# car.net
KiCad netlist of a schematic drawn in EAGLE
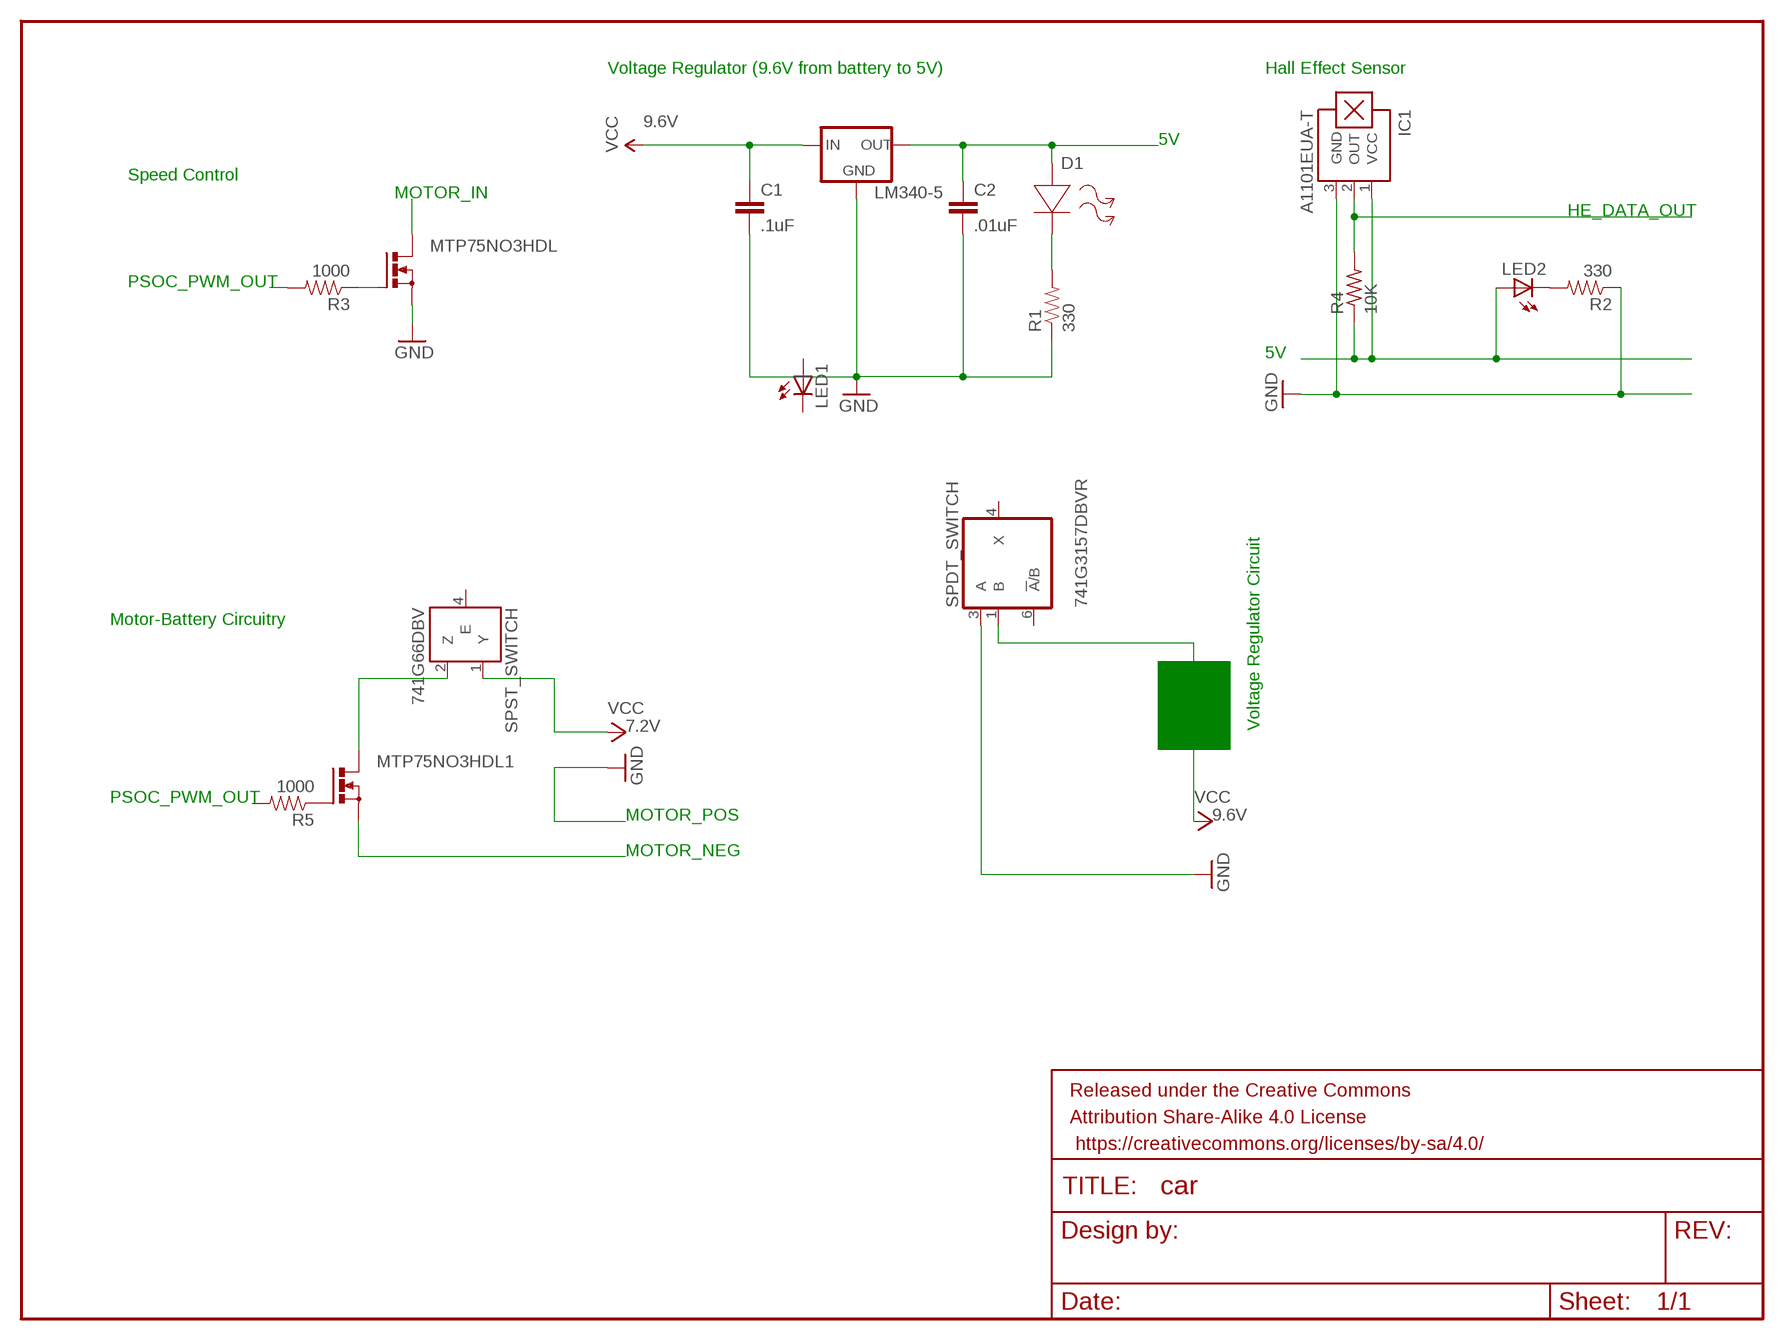
[diagram p0: schematic, sheet 1]

(export (version "E")
  (design (tool "Eeschema 10.0.6"))
  (components
    (comp (ref "C1")
      (value ".1uF")
      (footprint "eagle-import:0402-CAP")
      (libsource (lib "eagle-import") (part "CAP0402-CAP"))
    )
    (comp (ref "C2")
      (value ".01uF")
      (footprint "eagle-import:0402-CAP")
      (libsource (lib "eagle-import") (part "CAP0402-CAP"))
    )
    (comp (ref "D1")
      (value "LED")
      (footprint "eagle-import:R0805")
      (libsource (lib "eagle-import") (part "LED"))
    )
    (comp (ref "FRAME1")
      (value "FRAME-LETTER")
      (footprint "eagle-import:CREATIVE_COMMONS")
      (fields (field (name "DESIGNER") "NAME"))
      (libsource (lib "eagle-import") (part "FRAME-LETTER"))
    )
    (comp (ref "IC1")
      (value "A1101EUA-T")
      (footprint "eagle-import:SOT23-W")
      (fields (field (name "MF") "ALLEGRO MICROSYSTEMS, INC.") (field (name "MPN") "A1301ELHLT-T"))
      (libsource (lib "eagle-import") (part "A13?LH01"))
    )
    (comp (ref "LED1")
      (value "LED_E")
      (footprint "eagle-import:LED_1206")
      (libsource (lib "eagle-import") (part "LED_E"))
    )
    (comp (ref "LED2")
      (value "LED_E")
      (footprint "eagle-import:LED_1206")
      (libsource (lib "eagle-import") (part "LED_E"))
    )
    (comp (ref "LM340-5")
      (value "V_REG_78XX-TO-220")
      (footprint "eagle-import:TO-220-ALT")
      (libsource (lib "eagle-import") (part "V_REG_78XX-TO-220"))
    )
    (comp (ref "MTP75NO3HDL")
      (value "PMOSFET_NTO220BH")
      (footprint "eagle-import:TO220BH")
      (libsource (lib "eagle-import") (part "PMOSFET_NTO220BH"))
    )
    (comp (ref "MTP75NO3HDL1")
      (value "PMOSFET_NTO220BH")
      (footprint "eagle-import:TO220BH")
      (libsource (lib "eagle-import") (part "PMOSFET_NTO220BH"))
    )
    (comp (ref "R1")
      (value "330")
      (footprint "eagle-import:0402-RES")
      (libsource (lib "eagle-import") (part "RESISTOR0402-RES"))
    )
    (comp (ref "R2")
      (value "330")
      (footprint "eagle-import:0402-RES")
      (libsource (lib "eagle-import") (part "RESISTOR0402-RES"))
    )
    (comp (ref "R3")
      (value "1000")
      (footprint "eagle-import:0402-RES")
      (libsource (lib "eagle-import") (part "RESISTOR0402-RES"))
    )
    (comp (ref "R4")
      (value "10K")
      (footprint "eagle-import:0204V")
      (libsource (lib "eagle-import") (part "R-US_0204/2V"))
    )
    (comp (ref "R5")
      (value "1000")
      (footprint "eagle-import:0402-RES")
      (libsource (lib "eagle-import") (part "RESISTOR0402-RES"))
    )
    (comp (ref "SPDT_SWITCH")
      (value "741G3157DBVR")
      (footprint "eagle-import:DBV_R-PDSO-G6")
      (libsource (lib "eagle-import") (part "741G3157DBVR"))
    )
    (comp (ref "SPST_SWITCH")
      (value "741G66DBV")
      (footprint "eagle-import:SOT23-5")
      (libsource (lib "eagle-import") (part "741G66DBV"))
    )
  )
  (nets
    (net (code "1") (name "GND") (class "Default")
      (node (ref "C1") (pin "2") (pinfunction "2_2") (pintype "passive"))
      (node (ref "C2") (pin "2") (pinfunction "2_2") (pintype "passive"))
      (node (ref "IC1") (pin "3") (pinfunction "GND_3") (pintype "power_in"))
      (node (ref "LM340-5") (pin "GND") (pinfunction "GND_GND") (pintype "input"))
      (node (ref "MTP75NO3HDL") (pin "S") (pinfunction "S_S") (pintype "passive"))
      (node (ref "R1") (pin "1") (pinfunction "1_1") (pintype "passive"))
      (node (ref "R2") (pin "1") (pinfunction "1_1") (pintype "passive"))
      (node (ref "SPDT_SWITCH") (pin "3") (pinfunction "A_3") (pintype "bidirectional"))
    )
    (net (code "2") (name "Net-(D1-+)") (class "Default")
      (node (ref "C2") (pin "1") (pinfunction "1_1") (pintype "passive"))
      (node (ref "D1") (pin "1") (pinfunction "+_1") (pintype "passive"))
      (node (ref "LM340-5") (pin "OUT") (pinfunction "OUT_OUT") (pintype "output"))
    )
    (net (code "3") (name "Net-(D1--)") (class "Default")
      (node (ref "D1") (pin "2") (pinfunction "-_2") (pintype "passive"))
      (node (ref "R1") (pin "2") (pinfunction "2_2") (pintype "passive"))
    )
    (net (code "4") (name "Net-(IC1-OUT)") (class "Default")
      (node (ref "IC1") (pin "2") (pinfunction "OUT_2") (pintype "output"))
      (node (ref "R4") (pin "2") (pinfunction "2_2") (pintype "passive"))
    )
    (net (code "5") (name "Net-(IC1-VCC)") (class "Default")
      (node (ref "IC1") (pin "1") (pinfunction "VCC_1") (pintype "power_in"))
      (node (ref "LED2") (pin "A") (pinfunction "A_A") (pintype "passive"))
      (node (ref "R4") (pin "1") (pinfunction "1_1") (pintype "passive"))
    )
    (net (code "6") (name "Net-(LED2-PadC)") (class "Default")
      (node (ref "LED2") (pin "C") (pinfunction "C_C") (pintype "passive"))
      (node (ref "R2") (pin "2") (pinfunction "2_2") (pintype "passive"))
    )
    (net (code "7") (name "Net-(MTP75NO3HDL-PadG)") (class "Default")
      (node (ref "MTP75NO3HDL") (pin "G") (pinfunction "G_G") (pintype "passive"))
      (node (ref "R3") (pin "1") (pinfunction "1_1") (pintype "passive"))
    )
    (net (code "8") (name "Net-(MTP75NO3HDL1-PadG)") (class "Default")
      (node (ref "MTP75NO3HDL1") (pin "G") (pinfunction "G_G") (pintype "passive"))
      (node (ref "R5") (pin "1") (pinfunction "1_1") (pintype "passive"))
    )
    (net (code "9") (name "Net-(SPST_SWITCHA-Z)") (class "Default")
      (node (ref "MTP75NO3HDL1") (pin "D") (pinfunction "D_D") (pintype "passive"))
      (node (ref "SPST_SWITCH") (pin "2") (pinfunction "Z_2") (pintype "bidirectional"))
    )
    (net (code "10") (name "VCC") (class "Default")
      (node (ref "C1") (pin "1") (pinfunction "1_1") (pintype "passive"))
      (node (ref "LM340-5") (pin "IN") (pinfunction "IN_IN") (pintype "input"))
      (node (ref "SPST_SWITCH") (pin "1") (pinfunction "Y_1") (pintype "bidirectional"))
    )
    (net (code "11") (name "unconnected-(LED1-PadA)") (class "Default")
      (node (ref "LED1") (pin "A") (pinfunction "A_A") (pintype "passive"))
    )
    (net (code "12") (name "unconnected-(LED1-PadC)") (class "Default")
      (node (ref "LED1") (pin "C") (pinfunction "C_C") (pintype "passive"))
    )
    (net (code "13") (name "unconnected-(MTP75NO3HDL-PadD)") (class "Default")
      (node (ref "MTP75NO3HDL") (pin "D") (pinfunction "D_D") (pintype "passive"))
    )
    (net (code "14") (name "unconnected-(MTP75NO3HDL1-PadS)") (class "Default")
      (node (ref "MTP75NO3HDL1") (pin "S") (pinfunction "S_S") (pintype "passive"))
    )
    (net (code "15") (name "unconnected-(R3-Pad2)") (class "Default")
      (node (ref "R3") (pin "2") (pinfunction "2_2") (pintype "passive"))
    )
    (net (code "16") (name "unconnected-(R5-Pad2)") (class "Default")
      (node (ref "R5") (pin "2") (pinfunction "2_2") (pintype "passive"))
    )
    (net (code "17") (name "unconnected-(SPDT_SWITCHA-B-Pad1)") (class "Default")
      (node (ref "SPDT_SWITCH") (pin "1") (pinfunction "B_1") (pintype "bidirectional"))
    )
    (net (code "18") (name "unconnected-(SPDT_SWITCHA-X-Pad4)") (class "Default")
      (node (ref "SPDT_SWITCH") (pin "4") (pinfunction "X_4") (pintype "bidirectional"))
    )
    (net (code "19") (name "unconnected-(SPDT_SWITCHA-~{A}{slash}B-Pad6)") (class "Default")
      (node (ref "SPDT_SWITCH") (pin "6") (pinfunction "~{A}/B_6") (pintype "input"))
    )
    (net (code "20") (name "unconnected-(SPST_SWITCHA-E-Pad4)") (class "Default")
      (node (ref "SPST_SWITCH") (pin "4") (pinfunction "E_4") (pintype "input"))
    )
  )
)
